# CAM_Connector.net
KiCad netlist of a schematic drawn in Altium Designer
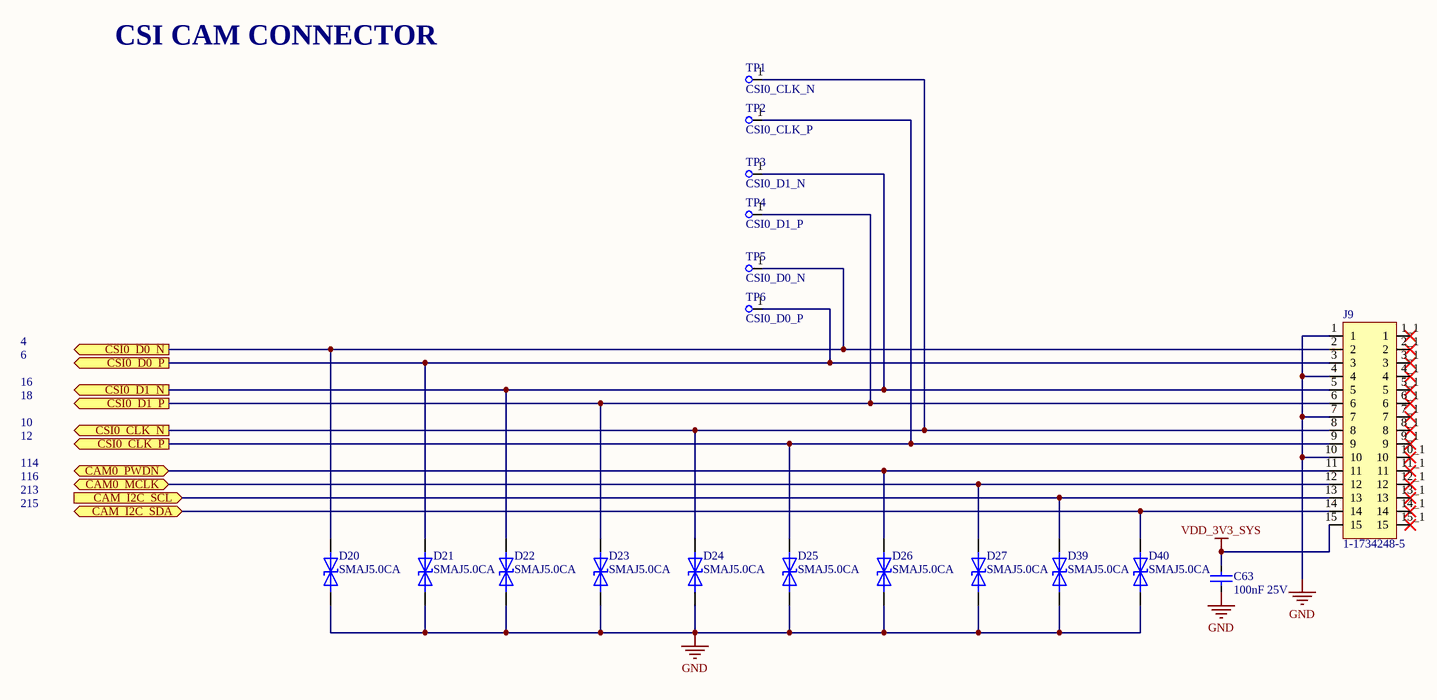
[diagram p0: CAM_Connector.SchDoc]

(export (version "E")
  (design (tool "Eeschema 10.0.6"))
  (components
    (comp (ref "C63")
      (value "100nF 25V")
      (footprint "C0402")
      (description "CAP CER 0.1UF 25V X5R 0402 / High Value Multilayer Ceramic Capacitors (High dielectric type)")
      (fields
        (field (name "MANUFACTURER") "Taiyo Yuden")
        (field (name "MANUFACTURER PART NUMBER") "TMK105BJ104KV-F")
      )
      (libsource (lib "GM_Altium_Library") (part "TMK105BJ104KV-F"))
    )
    (comp (ref "D20")
      (value "SMAJ5.0CA")
      (footprint "DO-214AC")
      (fields (field (name "MANUFACTURER") "Littelfuse"))
      (libsource (lib "GM_Altium_Library") (part "SMAJ5.0CA"))
    )
    (comp (ref "D21")
      (value "SMAJ5.0CA")
      (footprint "DO-214AC")
      (fields (field (name "MANUFACTURER") "Littelfuse"))
      (libsource (lib "GM_Altium_Library") (part "SMAJ5.0CA"))
    )
    (comp (ref "D22")
      (value "SMAJ5.0CA")
      (footprint "DO-214AC")
      (fields (field (name "MANUFACTURER") "Littelfuse"))
      (libsource (lib "GM_Altium_Library") (part "SMAJ5.0CA"))
    )
    (comp (ref "D23")
      (value "SMAJ5.0CA")
      (footprint "DO-214AC")
      (fields (field (name "MANUFACTURER") "Littelfuse"))
      (libsource (lib "GM_Altium_Library") (part "SMAJ5.0CA"))
    )
    (comp (ref "D24")
      (value "SMAJ5.0CA")
      (footprint "DO-214AC")
      (fields (field (name "MANUFACTURER") "Littelfuse"))
      (libsource (lib "GM_Altium_Library") (part "SMAJ5.0CA"))
    )
    (comp (ref "D25")
      (value "SMAJ5.0CA")
      (footprint "DO-214AC")
      (fields (field (name "MANUFACTURER") "Littelfuse"))
      (libsource (lib "GM_Altium_Library") (part "SMAJ5.0CA"))
    )
    (comp (ref "D26")
      (value "SMAJ5.0CA")
      (footprint "DO-214AC")
      (fields (field (name "MANUFACTURER") "Littelfuse"))
      (libsource (lib "GM_Altium_Library") (part "SMAJ5.0CA"))
    )
    (comp (ref "D27")
      (value "SMAJ5.0CA")
      (footprint "DO-214AC")
      (fields (field (name "MANUFACTURER") "Littelfuse"))
      (libsource (lib "GM_Altium_Library") (part "SMAJ5.0CA"))
    )
    (comp (ref "D39")
      (value "SMAJ5.0CA")
      (footprint "DO-214AC")
      (fields (field (name "MANUFACTURER") "Littelfuse"))
      (libsource (lib "GM_Altium_Library") (part "SMAJ5.0CA"))
    )
    (comp (ref "D40")
      (value "SMAJ5.0CA")
      (footprint "DO-214AC")
      (fields (field (name "MANUFACTURER") "Littelfuse"))
      (libsource (lib "GM_Altium_Library") (part "SMAJ5.0CA"))
    )
    (comp (ref "J9")
      (value "1-1734248-5")
      (footprint "1-1734248-5")
      (description "FPC CONNECTOR, RECEPTACLE 15POS 1MMPITCH; Series: FPC; Gender: Receptacle; Pitch S")
      (fields (field (name "MANUFACTURER") "TE Connectivity"))
      (libsource (lib "GM_Altium_Library") (part "1-1734248-5"))
    )
    (comp (ref "TP1")
      (value "CSI0_CLK_N")
      (footprint "TestPoint_Pad_D1.0mm")
      (libsource (lib "GM_Altium_Library") (part "TestPoint_D1mm"))
    )
    (comp (ref "TP2")
      (value "CSI0_CLK_P")
      (footprint "TestPoint_Pad_D1.0mm")
      (libsource (lib "GM_Altium_Library") (part "TestPoint_D1mm"))
    )
    (comp (ref "TP3")
      (value "CSI0_D1_N")
      (footprint "TestPoint_Pad_D1.0mm")
      (libsource (lib "GM_Altium_Library") (part "TestPoint_D1mm"))
    )
    (comp (ref "TP4")
      (value "CSI0_D1_P")
      (footprint "TestPoint_Pad_D1.0mm")
      (libsource (lib "GM_Altium_Library") (part "TestPoint_D1mm"))
    )
    (comp (ref "TP5")
      (value "CSI0_D0_N")
      (footprint "TestPoint_Pad_D1.0mm")
      (libsource (lib "GM_Altium_Library") (part "TestPoint_D1mm"))
    )
    (comp (ref "TP6")
      (value "CSI0_D0_P")
      (footprint "TestPoint_Pad_D1.0mm")
      (libsource (lib "GM_Altium_Library") (part "TestPoint_D1mm"))
    )
  )
  (nets
    (net (code "1") (name "/CAM0_MCLK") (class "Default")
      (node (ref "D27") (pin "A") (pinfunction "A_A") (pintype "passive"))
      (node (ref "J9") (pin "12") (pinfunction "12_12") (pintype "passive"))
    )
    (net (code "2") (name "/CAM0_PWDN") (class "Default")
      (node (ref "D26") (pin "A") (pinfunction "A_A") (pintype "passive"))
      (node (ref "J9") (pin "11") (pinfunction "11_11") (pintype "passive"))
    )
    (net (code "3") (name "/CAM_I2C_SCL") (class "Default")
      (node (ref "D39") (pin "A") (pinfunction "A_A") (pintype "passive"))
      (node (ref "J9") (pin "13") (pinfunction "13_13") (pintype "passive"))
    )
    (net (code "4") (name "/CAM_I2C_SDA") (class "Default")
      (node (ref "D40") (pin "A") (pinfunction "A_A") (pintype "passive"))
      (node (ref "J9") (pin "14") (pinfunction "14_14") (pintype "passive"))
    )
    (net (code "5") (name "/CSI0_CLK_N") (class "Default")
      (node (ref "D24") (pin "A") (pinfunction "A_A") (pintype "passive"))
      (node (ref "J9") (pin "8") (pinfunction "8_8") (pintype "passive"))
      (node (ref "TP1") (pin "1") (pinfunction "1_1") (pintype "passive"))
    )
    (net (code "6") (name "/CSI0_CLK_P") (class "Default")
      (node (ref "D25") (pin "A") (pinfunction "A_A") (pintype "passive"))
      (node (ref "J9") (pin "9") (pinfunction "9_9") (pintype "passive"))
      (node (ref "TP2") (pin "1") (pinfunction "1_1") (pintype "passive"))
    )
    (net (code "7") (name "/CSI0_D0_N") (class "Default")
      (node (ref "D20") (pin "A") (pinfunction "A_A") (pintype "passive"))
      (node (ref "J9") (pin "2") (pinfunction "2_2") (pintype "passive"))
      (node (ref "TP5") (pin "1") (pinfunction "1_1") (pintype "passive"))
    )
    (net (code "8") (name "/CSI0_D0_P") (class "Default")
      (node (ref "D21") (pin "A") (pinfunction "A_A") (pintype "passive"))
      (node (ref "J9") (pin "3") (pinfunction "3_3") (pintype "passive"))
      (node (ref "TP6") (pin "1") (pinfunction "1_1") (pintype "passive"))
    )
    (net (code "9") (name "/CSI0_D1_N") (class "Default")
      (node (ref "D22") (pin "A") (pinfunction "A_A") (pintype "passive"))
      (node (ref "J9") (pin "5") (pinfunction "5_5") (pintype "passive"))
      (node (ref "TP3") (pin "1") (pinfunction "1_1") (pintype "passive"))
    )
    (net (code "10") (name "/CSI0_D1_P") (class "Default")
      (node (ref "D23") (pin "A") (pinfunction "A_A") (pintype "passive"))
      (node (ref "J9") (pin "6") (pinfunction "6_6") (pintype "passive"))
      (node (ref "TP4") (pin "1") (pinfunction "1_1") (pintype "passive"))
    )
    (net (code "11") (name "GND") (class "Default")
      (node (ref "C63") (pin "1") (pinfunction "1_1") (pintype "passive"))
      (node (ref "D20") (pin "C") (pinfunction "C_C") (pintype "passive"))
      (node (ref "D21") (pin "C") (pinfunction "C_C") (pintype "passive"))
      (node (ref "D22") (pin "C") (pinfunction "C_C") (pintype "passive"))
      (node (ref "D23") (pin "C") (pinfunction "C_C") (pintype "passive"))
      (node (ref "D24") (pin "C") (pinfunction "C_C") (pintype "passive"))
      (node (ref "D25") (pin "C") (pinfunction "C_C") (pintype "passive"))
      (node (ref "D26") (pin "C") (pinfunction "C_C") (pintype "passive"))
      (node (ref "D27") (pin "C") (pinfunction "C_C") (pintype "passive"))
      (node (ref "D39") (pin "C") (pinfunction "C_C") (pintype "passive"))
      (node (ref "D40") (pin "C") (pinfunction "C_C") (pintype "passive"))
      (node (ref "J9") (pin "1") (pinfunction "1_1") (pintype "passive"))
      (node (ref "J9") (pin "10") (pinfunction "10_10") (pintype "passive"))
      (node (ref "J9") (pin "4") (pinfunction "4_4") (pintype "passive"))
      (node (ref "J9") (pin "7") (pinfunction "7_7") (pintype "passive"))
    )
    (net (code "12") (name "VDD_3V3_SYS") (class "Default")
      (node (ref "C63") (pin "2") (pinfunction "2_2") (pintype "passive"))
      (node (ref "J9") (pin "15") (pinfunction "15_15") (pintype "passive"))
    )
    (net (code "13") (name "unconnected-(J9-1-Pad1_1)") (class "Default")
      (node (ref "J9") (pin "1_1") (pinfunction "1_1_1") (pintype "passive+no_connect"))
    )
    (net (code "14") (name "unconnected-(J9-2-Pad2_1)") (class "Default")
      (node (ref "J9") (pin "2_1") (pinfunction "2_2_1") (pintype "passive+no_connect"))
    )
    (net (code "15") (name "unconnected-(J9-3-Pad3_1)") (class "Default")
      (node (ref "J9") (pin "3_1") (pinfunction "3_3_1") (pintype "passive+no_connect"))
    )
    (net (code "16") (name "unconnected-(J9-4-Pad4_1)") (class "Default")
      (node (ref "J9") (pin "4_1") (pinfunction "4_4_1") (pintype "passive+no_connect"))
    )
    (net (code "17") (name "unconnected-(J9-5-Pad5_1)") (class "Default")
      (node (ref "J9") (pin "5_1") (pinfunction "5_5_1") (pintype "passive+no_connect"))
    )
    (net (code "18") (name "unconnected-(J9-6-Pad6_1)") (class "Default")
      (node (ref "J9") (pin "6_1") (pinfunction "6_6_1") (pintype "passive+no_connect"))
    )
    (net (code "19") (name "unconnected-(J9-7-Pad7_1)") (class "Default")
      (node (ref "J9") (pin "7_1") (pinfunction "7_7_1") (pintype "passive+no_connect"))
    )
    (net (code "20") (name "unconnected-(J9-8-Pad8_1)") (class "Default")
      (node (ref "J9") (pin "8_1") (pinfunction "8_8_1") (pintype "passive+no_connect"))
    )
    (net (code "21") (name "unconnected-(J9-9-Pad9_1)") (class "Default")
      (node (ref "J9") (pin "9_1") (pinfunction "9_9_1") (pintype "passive+no_connect"))
    )
    (net (code "22") (name "unconnected-(J9-10-Pad10_1)") (class "Default")
      (node (ref "J9") (pin "10_1") (pinfunction "10_10_1") (pintype "passive+no_connect"))
    )
    (net (code "23") (name "unconnected-(J9-11-Pad11_1)") (class "Default")
      (node (ref "J9") (pin "11_1") (pinfunction "11_11_1") (pintype "passive+no_connect"))
    )
    (net (code "24") (name "unconnected-(J9-12-Pad12_1)") (class "Default")
      (node (ref "J9") (pin "12_1") (pinfunction "12_12_1") (pintype "passive+no_connect"))
    )
    (net (code "25") (name "unconnected-(J9-13-Pad13_1)") (class "Default")
      (node (ref "J9") (pin "13_1") (pinfunction "13_13_1") (pintype "passive+no_connect"))
    )
    (net (code "26") (name "unconnected-(J9-14-Pad14_1)") (class "Default")
      (node (ref "J9") (pin "14_1") (pinfunction "14_14_1") (pintype "passive+no_connect"))
    )
    (net (code "27") (name "unconnected-(J9-15-Pad15_1)") (class "Default")
      (node (ref "J9") (pin "15_1") (pinfunction "15_15_1") (pintype "passive+no_connect"))
    )
  )
)
